# speaker.net
KiCad netlist of a schematic drawn in Altium Designer
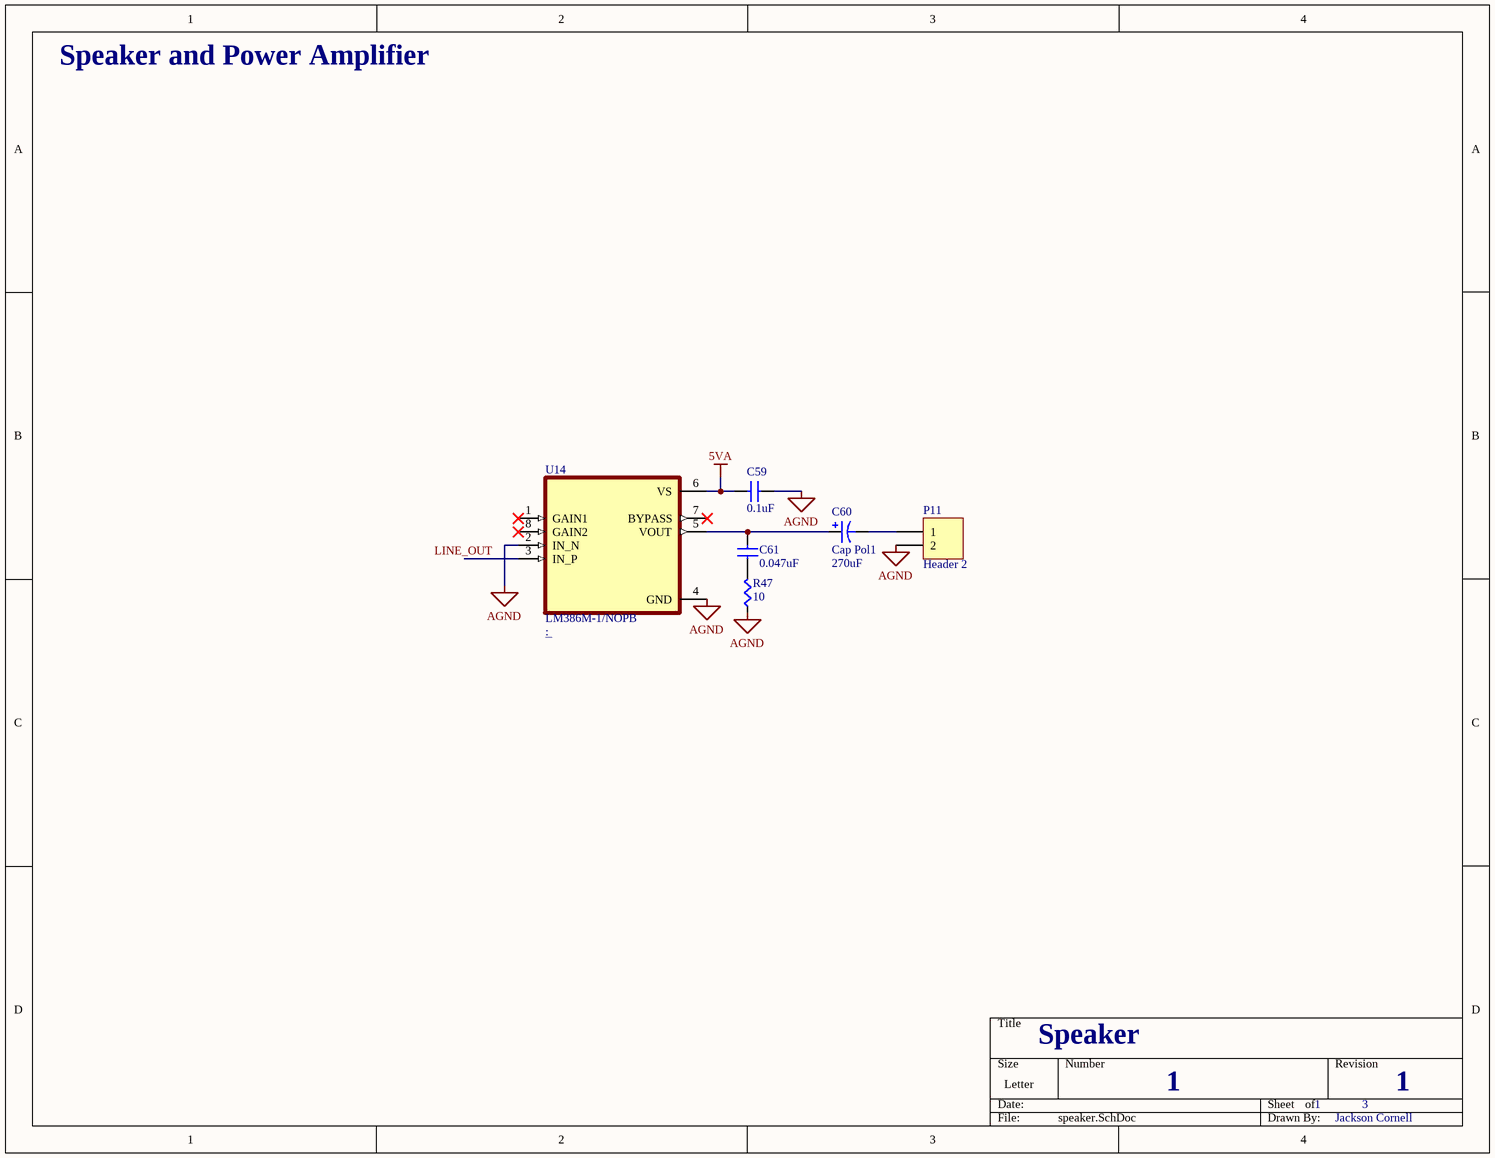
[diagram p0: speaker.SchDoc]

(export (version "E")
  (design (tool "Eeschema 10.0.6"))
  (components
    (comp (ref "C59")
      (value "0.1uF")
      (footprint "CAPC0805")
      (fields (field (name "Comment") "Cap"))
      (libsource (lib "Passives") (part "Cap"))
    )
    (comp (ref "C60")
      (value "Cap Pol1")
      (footprint "CAPC0805")
      (description "Polarized Capacitor (Radial)")
      (fields (field (name "ALTIUM_VALUE") "270uF") (field (name "PUBLISHER") "Altium Limited"))
      (libsource (lib "Miscellaneous Devices") (part "Cap Pol1"))
    )
    (comp (ref "C61")
      (value "0.047uF")
      (footprint "CAPC0805")
      (fields (field (name "Comment") "Cap"))
      (libsource (lib "Passives") (part "Cap"))
    )
    (comp (ref "P11")
      (value "Header 2")
      (footprint "HDR1X2")
      (description "Header, 2-Pin")
      (fields (field (name "PUBLISHER") "Altium Limited"))
      (libsource (lib "Miscellaneous Connectors") (part "Header 2"))
    )
    (comp (ref "R47")
      (value "10")
      (footprint "RES0805")
      (fields (field (name "Comment") "Res"))
      (libsource (lib "Passives") (part "Res"))
    )
    (comp (ref "U14")
      (value "LM386M-1/NOPB")
      (footprint "SOIC127P599X175-8N")
      (description "Wide Input Voltage Low Power Audio Amplifier with Internal Gain")
      (fields (field (name "MP") "LM386M-1") (field (name "MF") "Texas Instruments"))
      (libsource (lib "LM386M-1_NOPB") (part "LM386M-1/NOPB"))
    )
  )
  (nets
    (net (code "1") (name "/LINE_OUT") (class "Default")
      (node (ref "U14") (pin "3") (pinfunction "IN_P_3") (pintype "input"))
    )
    (net (code "2") (name "5VA") (class "Default")
      (node (ref "C59") (pin "2") (pinfunction "B_2") (pintype "passive"))
      (node (ref "U14") (pin "6") (pinfunction "VS_6") (pintype "power_in"))
    )
    (net (code "3") (name "AGND") (class "Default")
      (node (ref "C59") (pin "1") (pinfunction "A_1") (pintype "passive"))
      (node (ref "P11") (pin "2") (pinfunction "2_2") (pintype "passive"))
      (node (ref "R47") (pin "2") (pinfunction "B_2") (pintype "passive"))
      (node (ref "U14") (pin "2") (pinfunction "IN_N_2") (pintype "input"))
      (node (ref "U14") (pin "4") (pinfunction "GND_4") (pintype "power_in"))
    )
    (net (code "4") (name "Net-(C60-Pad2)") (class "Default")
      (node (ref "C60") (pin "2") (pinfunction "2_2") (pintype "passive"))
      (node (ref "P11") (pin "1") (pinfunction "1_1") (pintype "passive"))
    )
    (net (code "5") (name "Net-(C61-A)") (class "Default")
      (node (ref "C60") (pin "1") (pinfunction "1_1") (pintype "passive"))
      (node (ref "C61") (pin "1") (pinfunction "A_1") (pintype "passive"))
      (node (ref "U14") (pin "5") (pinfunction "VOUT_5") (pintype "output"))
    )
    (net (code "6") (name "Net-(C61-B)") (class "Default")
      (node (ref "C61") (pin "2") (pinfunction "B_2") (pintype "passive"))
      (node (ref "R47") (pin "1") (pinfunction "A_1") (pintype "passive"))
    )
    (net (code "7") (name "unconnected-(U14-BYPASS-Pad7)") (class "Default")
      (node (ref "U14") (pin "7") (pinfunction "BYPASS_7") (pintype "output+no_connect"))
    )
    (net (code "8") (name "unconnected-(U14-GAIN1-Pad1)") (class "Default")
      (node (ref "U14") (pin "1") (pinfunction "GAIN1_1") (pintype "input+no_connect"))
    )
    (net (code "9") (name "unconnected-(U14-GAIN2-Pad8)") (class "Default")
      (node (ref "U14") (pin "8") (pinfunction "GAIN2_8") (pintype "input+no_connect"))
    )
  )
)
